# Umwandlung_1_8_to_5_V2.net
KiCad netlist of a schematic drawn in EAGLE
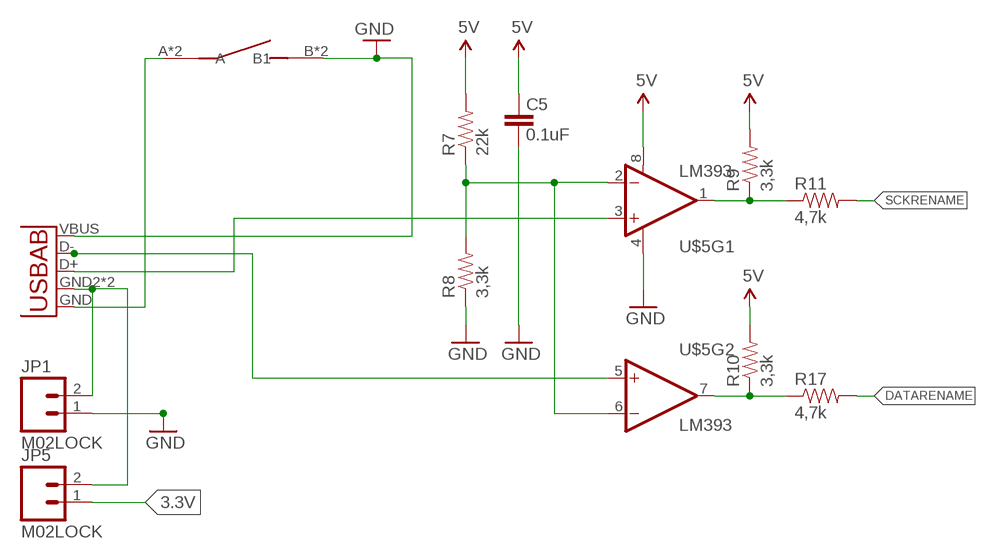
[diagram p0: schematic, sheet 1]

(export (version "E")
  (design (tool "Eeschema 10.0.6"))
  (components
    (comp (ref "C5")
      (value "0.1uF")
      (footprint "eagle-import:0805")
      (libsource (lib "eagle-import") (part "CAP0805"))
    )
    (comp (ref "JP1")
      (value "M02LOCK")
      (footprint "eagle-import:1X02_LOCK")
      (libsource (lib "eagle-import") (part "M02LOCK"))
    )
    (comp (ref "JP5")
      (value "M02LOCK")
      (footprint "eagle-import:1X02_LOCK")
      (libsource (lib "eagle-import") (part "M02LOCK"))
    )
    (comp (ref "R7")
      (value "22k")
      (footprint "eagle-import:0805")
      (libsource (lib "eagle-import") (part "RESISTOR"))
    )
    (comp (ref "R8")
      (value "3,3k")
      (footprint "eagle-import:0805")
      (libsource (lib "eagle-import") (part "RESISTOR"))
    )
    (comp (ref "R9")
      (value "3,3k")
      (footprint "eagle-import:0805")
      (libsource (lib "eagle-import") (part "RESISTOR"))
    )
    (comp (ref "R10")
      (value "3,3k")
      (footprint "eagle-import:0805")
      (libsource (lib "eagle-import") (part "RESISTOR"))
    )
    (comp (ref "R11")
      (value "4,7k")
      (footprint "eagle-import:0805")
      (libsource (lib "eagle-import") (part "RESISTOR"))
    )
    (comp (ref "R17")
      (value "4,7k")
      (footprint "eagle-import:0805")
      (libsource (lib "eagle-import") (part "RESISTOR"))
    )
    (comp (ref "U$1")
      (value "TASTE_R3FTL6")
      (footprint "eagle-import:TASTE_R3FTL6")
      (libsource (lib "eagle-import") (part "TASTE_R3FTL6"))
    )
    (comp (ref "U$5")
      (value "LM393")
      (footprint "eagle-import:SO08")
      (libsource (lib "eagle-import") (part "LM393"))
    )
    (comp (ref "U$7")
      (value "USB-A")
      (footprint "eagle-import:USB-A")
      (libsource (lib "eagle-import") (part "USB-A"))
    )
  )
  (nets
    (net (code "1") (name "3.3V") (class "Default")
      (node (ref "JP5") (pin "1") (pinfunction "1_1") (pintype "passive"))
    )
    (net (code "2") (name "5V") (class "Default")
      (node (ref "C5") (pin "2") (pinfunction "2_2") (pintype "passive"))
      (node (ref "R10") (pin "2") (pinfunction "2_2") (pintype "passive"))
      (node (ref "R7") (pin "2") (pinfunction "2_2") (pintype "passive"))
      (node (ref "R9") (pin "2") (pinfunction "2_2") (pintype "passive"))
      (node (ref "U$5") (pin "8") (pinfunction "V+_8") (pintype "power_in"))
    )
    (net (code "3") (name "DATARENAME") (class "Default")
      (node (ref "R17") (pin "2") (pinfunction "2_2") (pintype "passive"))
    )
    (net (code "4") (name "GND") (class "Default")
      (node (ref "C5") (pin "1") (pinfunction "1_1") (pintype "passive"))
      (node (ref "JP1") (pin "1") (pinfunction "1_1") (pintype "passive"))
      (node (ref "R8") (pin "1") (pinfunction "1_1") (pintype "passive"))
      (node (ref "U$1") (pin "B") (pinfunction "B1_B") (pintype "bidirectional"))
      (node (ref "U$1") (pin "B1") (pinfunction "B1_B1") (pintype "bidirectional"))
      (node (ref "U$5") (pin "4") (pinfunction "V-_4") (pintype "power_in"))
      (node (ref "U$7") (pin "VBUS") (pinfunction "VBUS_VBUS") (pintype "bidirectional"))
    )
    (net (code "5") (name "Net-(JP1-Pad2)") (class "Default")
      (node (ref "JP1") (pin "2") (pinfunction "2_2") (pintype "passive"))
      (node (ref "JP5") (pin "2") (pinfunction "2_2") (pintype "passive"))
      (node (ref "U$7") (pin "GND2") (pinfunction "USBID_GND2") (pintype "bidirectional"))
      (node (ref "U$7") (pin "GND3") (pinfunction "USBID_GND3") (pintype "bidirectional"))
    )
    (net (code "6") (name "Net-(U$1-A-PadA1)") (class "Default")
      (node (ref "U$1") (pin "A") (pinfunction "A_A") (pintype "bidirectional"))
      (node (ref "U$1") (pin "A1") (pinfunction "A_A1") (pintype "bidirectional"))
      (node (ref "U$7") (pin "GND") (pinfunction "GND_GND") (pintype "bidirectional"))
    )
    (net (code "7") (name "Net-(U$5A-+IN)") (class "Default")
      (node (ref "U$5") (pin "3") (pinfunction "+IN_3") (pintype "input"))
      (node (ref "U$7") (pin "D+") (pinfunction "D+_D+") (pintype "bidirectional"))
    )
    (net (code "8") (name "Net-(U$5A--IN)") (class "Default")
      (node (ref "R7") (pin "1") (pinfunction "1_1") (pintype "passive"))
      (node (ref "R8") (pin "2") (pinfunction "2_2") (pintype "passive"))
      (node (ref "U$5") (pin "2") (pinfunction "-IN_2") (pintype "input"))
      (node (ref "U$5") (pin "6") (pinfunction "-IN_6") (pintype "input"))
    )
    (net (code "9") (name "Net-(U$5A-OUT)") (class "Default")
      (node (ref "R11") (pin "1") (pinfunction "1_1") (pintype "passive"))
      (node (ref "R9") (pin "1") (pinfunction "1_1") (pintype "passive"))
      (node (ref "U$5") (pin "1") (pinfunction "OUT_1") (pintype "output"))
    )
    (net (code "10") (name "Net-(U$5B-+IN)") (class "Default")
      (node (ref "U$5") (pin "5") (pinfunction "+IN_5") (pintype "input"))
      (node (ref "U$7") (pin "D-") (pinfunction "D-_D-") (pintype "bidirectional"))
    )
    (net (code "11") (name "Net-(U$5B-OUT)") (class "Default")
      (node (ref "R10") (pin "1") (pinfunction "1_1") (pintype "passive"))
      (node (ref "R17") (pin "1") (pinfunction "1_1") (pintype "passive"))
      (node (ref "U$5") (pin "7") (pinfunction "OUT_7") (pintype "output"))
    )
    (net (code "12") (name "SCKRENAME") (class "Default")
      (node (ref "R11") (pin "2") (pinfunction "2_2") (pintype "passive"))
    )
  )
)
